# synchronous.net
KiCad netlist of a schematic drawn in Altium Designer
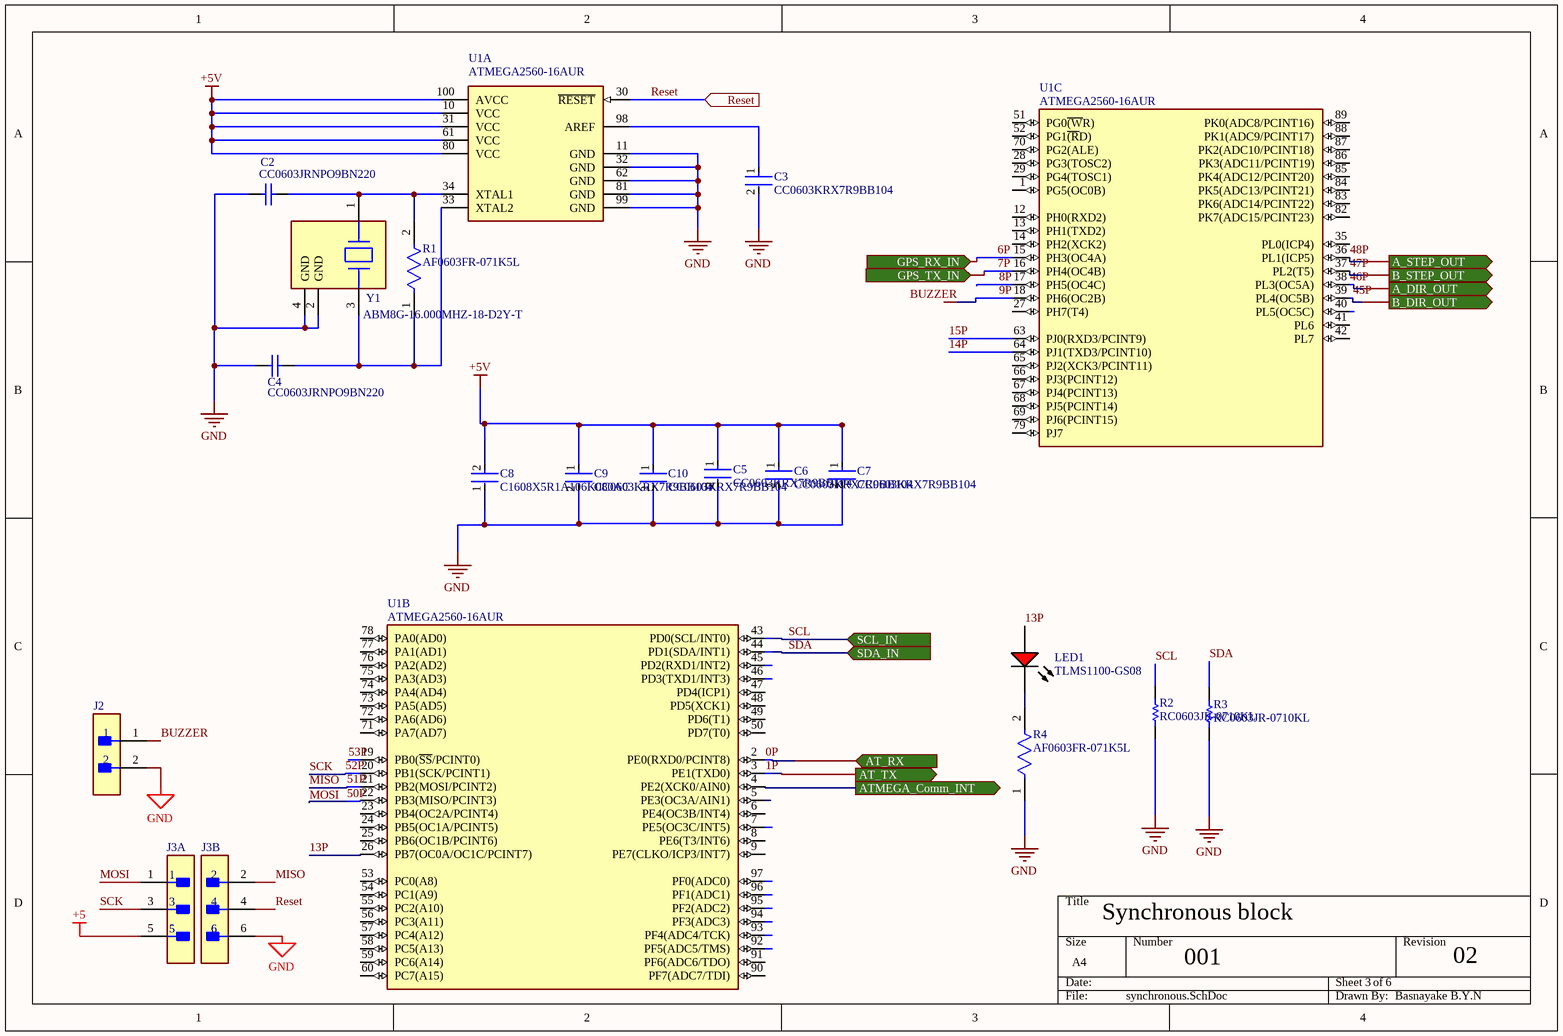
[diagram p0: synchronous.SchDoc]

(export (version "E")
  (design (tool "Eeschema 10.0.6"))
  (components
    (comp (ref "C2")
      (value "CC0603JRNPO9BN220")
      (footprint "CAPC1608X90X40LL10T20")
      (description "Chip Capacitor, 22 pF, +/- 5%, 50 V, -55 to 125 degC, 0603 (1608 Metric), RoHS, Tape and Reel")
      (libsource (lib "Altium Content Vault") (part "CAP-NP-2"))
    )
    (comp (ref "C3")
      (value "CC0603KRX7R9BB104")
      (footprint "FP-CC0603-DA-MFG")
      (description "CAP CER 0.1UF 50V X7R 0603")
      (fields (field (name "MANUFACTURER") "YAGEO") (field (name "VOLTAGE") "50 V"))
      (libsource (lib "Altium Content Vault") (part "11868f565c42a9108669ba33697ecf6"))
    )
    (comp (ref "C4")
      (value "CC0603JRNPO9BN220")
      (footprint "CAPC1608X90X40LL10T20")
      (description "Chip Capacitor, 22 pF, +/- 5%, 50 V, -55 to 125 degC, 0603 (1608 Metric), RoHS, Tape and Reel")
      (libsource (lib "Altium Content Vault") (part "CAP-NP-2"))
    )
    (comp (ref "C5")
      (value "CC0603KRX7R9BB104")
      (footprint "FP-CC0603-DA-MFG")
      (description "CAP CER 0.1UF 50V X7R 0603")
      (fields (field (name "MANUFACTURER") "YAGEO") (field (name "VOLTAGE") "50 V"))
      (libsource (lib "Altium Content Vault") (part "11868f565c42a9108669ba33697ecf6"))
    )
    (comp (ref "C6")
      (value "CC0603KRX7R9BB104")
      (footprint "FP-CC0603-DA-MFG")
      (description "CAP CER 0.1UF 50V X7R 0603")
      (fields (field (name "MANUFACTURER") "YAGEO") (field (name "VOLTAGE") "50 V"))
      (libsource (lib "Altium Content Vault") (part "11868f565c42a9108669ba33697ecf6"))
    )
    (comp (ref "C7")
      (value "CC0603KRX7R9BB104")
      (footprint "FP-CC0603-DA-MFG")
      (description "CAP CER 0.1UF 50V X7R 0603")
      (fields (field (name "MANUFACTURER") "YAGEO") (field (name "VOLTAGE") "50 V"))
      (libsource (lib "Altium Content Vault") (part "11868f565c42a9108669ba33697ecf6"))
    )
    (comp (ref "C8")
      (value "C1608X5R1A106K080AC")
      (footprint "FP-C1608-080-0_1-MFG")
      (description "Multilayer Ceramic Capacitors 10μF ±10% 10V X5R SMD 0603")
      (fields (field (name "VOLTAGE") "10V") (field (name "TOLERANCE") "10%"))
      (libsource (lib "Altium Content Vault") (part "236180d848d6139a670b325ea6854c9"))
    )
    (comp (ref "C9")
      (value "CC0603KRX7R9BB104")
      (footprint "FP-CC0603-DA-MFG")
      (description "CAP CER 0.1UF 50V X7R 0603")
      (fields (field (name "MANUFACTURER") "YAGEO") (field (name "VOLTAGE") "50 V"))
      (libsource (lib "Altium Content Vault") (part "11868f565c42a9108669ba33697ecf6"))
    )
    (comp (ref "C10")
      (value "CC0603KRX7R9BB104")
      (footprint "FP-CC0603-DA-MFG")
      (description "CAP CER 0.1UF 50V X7R 0603")
      (fields (field (name "MANUFACTURER") "YAGEO") (field (name "VOLTAGE") "50 V"))
      (libsource (lib "Altium Content Vault") (part "11868f565c42a9108669ba33697ecf6"))
    )
    (comp (ref "J2")
      (value "B2B-XH-A(LF)(SN)")
      (footprint "FP-B2B-XH-A_LF_SN-MFG")
      (description "CONN HEADER VERT 2POS 2.5MM")
      (libsource (lib "Altium Content Vault") (part "3bc925449376181038e59eaffc5286c"))
    )
    (comp (ref "J3")
      (value "M20-9980346")
      (footprint "FP-M20-9980346-MFG")
      (description "CONN HEADER VERT 6POS 2.54MM")
      (fields
        (field (name "MANUFACTURER") "Harwin")
        (field (name "OCTOPART") "https://octopart.com/m20-9980346-harwin-5436545")
      )
      (libsource (lib "") (part "2654a11fb13586ecb194516b1c997bc_1"))
    )
    (comp (ref "LED1")
      (value "TLMS1100-GS08")
      (footprint "VISH-TLMX1100_V")
      (description "LED, RED, 2.1 V, -40 to 100 degC, 2-Pin SMD (0603), RoHS, Tape and Reel")
      (fields (field (name "TOLERANCE") "5%"))
      (libsource (lib "Altium Content Vault") (part "LED-RED-AK-2"))
    )
    (comp (ref "R1")
      (value "AF0603FR-071K5L")
      (footprint "FP-AF0603-IPC_B")
      (description "Anti-Sulfurated Chip Resistors Automotive Grade 1.5kΩ 1% 100ppm/°C 0603")
      (fields (field (name "TOLERANCE") "1%"))
      (libsource (lib "Altium Content Vault") (part "1029c3af85768c4190bb7ad29bc67b5"))
    )
    (comp (ref "R2")
      (value "RC0603JR-0710KL")
      (footprint "RESC1608X55X25ML10T15")
      (description "Resistor, 10 KOhm, +/- 5%, 100 mW, -55 to 155 degC, 0603 (1608 Metric), RoHS, Tape and Reel")
      (fields (field (name "MANUFACTURER") "Yageo") (field (name "TOLERANCE") "5%"))
      (libsource (lib "Altium Content Vault") (part "RES-2"))
    )
    (comp (ref "R3")
      (value "RC0603JR-0710KL")
      (footprint "RESC1608X55X25ML10T15")
      (description "Resistor, 10 KOhm, +/- 5%, 100 mW, -55 to 155 degC, 0603 (1608 Metric), RoHS, Tape and Reel")
      (fields (field (name "MANUFACTURER") "Yageo") (field (name "TOLERANCE") "5%"))
      (libsource (lib "Altium Content Vault") (part "RES-2"))
    )
    (comp (ref "R4")
      (value "AF0603FR-071K5L")
      (footprint "FP-AF0603-IPC_B")
      (description "Anti-Sulfurated Chip Resistors Automotive Grade 1.5kΩ 1% 100ppm/°C 0603")
      (fields (field (name "TOLERANCE") "1%"))
      (libsource (lib "Altium Content Vault") (part "1029c3af85768c4190bb7ad29bc67b5"))
    )
    (comp (ref "U1")
      (value "ATMEGA2560-16AUR")
      (footprint "FP-100A-MFG")
      (description "IC MCU 8BIT 256KB FLASH 100TQFP")
      (libsource (lib "Altium Content Vault") (part "7a986b9e50de34ed0d2049ae6a26084"))
    )
    (comp (ref "Y1")
      (value "ABM8G-16.000MHZ-18-D2Y-T")
      (footprint "FP-ABM8G-MFG")
      (description "Crystal 12MHz ±20ppm (Tol) ±30ppm (Stability) 18pF FUND 120Ω 4-Pin SMD T/R")
      (fields (field (name "TOLERANCE") "20ppm"))
      (libsource (lib "Altium Content Vault") (part "48e526d86b7f2615d98721063c72f49"))
    )
  )
  (nets
    (net (code "1") (name "+5") (class "Default")
      (node (ref "J3") (pin "5") (pinfunction "5_5") (pintype "passive"))
    )
    (net (code "2") (name "+5V") (class "Default")
      (node (ref "C10") (pin "1") (pinfunction "1_1") (pintype "passive"))
      (node (ref "C5") (pin "1") (pinfunction "1_1") (pintype "passive"))
      (node (ref "C6") (pin "1") (pinfunction "1_1") (pintype "passive"))
      (node (ref "C7") (pin "1") (pinfunction "1_1") (pintype "passive"))
      (node (ref "C8") (pin "2") (pinfunction "2_2") (pintype "passive"))
      (node (ref "C9") (pin "1") (pinfunction "1_1") (pintype "passive"))
      (node (ref "U1") (pin "10") (pinfunction "VCC_10") (pintype "power_in"))
      (node (ref "U1") (pin "100") (pinfunction "AVCC_100") (pintype "power_in"))
      (node (ref "U1") (pin "31") (pinfunction "VCC_31") (pintype "power_in"))
      (node (ref "U1") (pin "61") (pinfunction "VCC_61") (pintype "power_in"))
      (node (ref "U1") (pin "80") (pinfunction "VCC_80") (pintype "power_in"))
    )
    (net (code "3") (name "/0P") (class "Default")
      (node (ref "U1") (pin "2") (pinfunction "PE0(RXD0/PCINT8)_2") (pintype "bidirectional"))
    )
    (net (code "4") (name "/1P") (class "Default")
      (node (ref "U1") (pin "3") (pinfunction "PE1(TXD0)_3") (pintype "bidirectional"))
    )
    (net (code "5") (name "/6P") (class "Default")
      (node (ref "U1") (pin "15") (pinfunction "PH3(OC4A)_15") (pintype "bidirectional"))
    )
    (net (code "6") (name "/7P") (class "Default")
      (node (ref "U1") (pin "16") (pinfunction "PH4(OC4B)_16") (pintype "bidirectional"))
    )
    (net (code "7") (name "/8P") (class "Default")
      (node (ref "U1") (pin "17") (pinfunction "PH5(OC4C)_17") (pintype "bidirectional"))
    )
    (net (code "8") (name "/9P") (class "Default")
      (node (ref "U1") (pin "18") (pinfunction "PH6(OC2B)_18") (pintype "bidirectional"))
    )
    (net (code "9") (name "/13P") (class "Default")
      (node (ref "LED1") (pin "1") (pinfunction "A_1") (pintype "passive"))
      (node (ref "U1") (pin "26") (pinfunction "PB7(OC0A/OC1C/PCINT7)_26") (pintype "bidirectional"))
    )
    (net (code "10") (name "/14P") (class "Default")
      (node (ref "U1") (pin "64") (pinfunction "PJ1(TXD3/PCINT10)_64") (pintype "bidirectional"))
    )
    (net (code "11") (name "/15P") (class "Default")
      (node (ref "U1") (pin "63") (pinfunction "PJ0(RXD3/PCINT9)_63") (pintype "bidirectional"))
    )
    (net (code "12") (name "/45P") (class "Default")
      (node (ref "U1") (pin "39") (pinfunction "PL4(OC5B)_39") (pintype "bidirectional"))
    )
    (net (code "13") (name "/46P") (class "Default")
      (node (ref "U1") (pin "38") (pinfunction "PL3(OC5A)_38") (pintype "bidirectional"))
    )
    (net (code "14") (name "/47P") (class "Default")
      (node (ref "U1") (pin "37") (pinfunction "PL2(T5)_37") (pintype "bidirectional"))
    )
    (net (code "15") (name "/48P") (class "Default")
      (node (ref "U1") (pin "36") (pinfunction "PL1(ICP5)_36") (pintype "bidirectional"))
    )
    (net (code "16") (name "/50P") (class "Default")
      (node (ref "J3") (pin "1") (pinfunction "1_1") (pintype "passive"))
      (node (ref "U1") (pin "22") (pinfunction "PB3(MISO/PCINT3)_22") (pintype "bidirectional"))
    )
    (net (code "18") (name "/52P") (class "Default")
      (node (ref "J3") (pin "3") (pinfunction "3_3") (pintype "passive"))
      (node (ref "U1") (pin "20") (pinfunction "PB1(SCK/PCINT1)_20") (pintype "bidirectional"))
    )
    (net (code "19") (name "/53P") (class "Default")
      (node (ref "U1") (pin "19") (pinfunction "PB0(~{SS}/PCINT0)_19") (pintype "bidirectional"))
    )
    (net (code "20") (name "/ATMEGA_Comm_INT") (class "Default")
      (node (ref "U1") (pin "4") (pinfunction "PE2(XCK0/AIN0)_4") (pintype "bidirectional"))
    )
    (net (code "21") (name "/BUZZER") (class "Default")
      (node (ref "J2") (pin "1") (pinfunction "1_1") (pintype "passive"))
    )
    (net (code "22") (name "/MISO") (class "Default")
      (node (ref "J3") (pin "2") (pinfunction "2_2") (pintype "passive"))
      (node (ref "U1") (pin "21") (pinfunction "PB2(MOSI/PCINT2)_21") (pintype "bidirectional"))
    )
    (net (code "23") (name "/Reset") (class "Default")
      (node (ref "J3") (pin "4") (pinfunction "4_4") (pintype "passive"))
      (node (ref "U1") (pin "30") (pinfunction "~{RESET}_30") (pintype "input"))
    )
    (net (code "24") (name "/SCL") (class "Default")
      (node (ref "R2") (pin "2") (pinfunction "2_2") (pintype "passive"))
      (node (ref "U1") (pin "43") (pinfunction "PD0(SCL/INT0)_43") (pintype "bidirectional"))
    )
    (net (code "25") (name "/SDA") (class "Default")
      (node (ref "R3") (pin "2") (pinfunction "2_2") (pintype "passive"))
      (node (ref "U1") (pin "44") (pinfunction "PD1(SDA/INT1)_44") (pintype "bidirectional"))
    )
    (net (code "26") (name "GND") (class "Default")
      (node (ref "C10") (pin "2") (pinfunction "2_2") (pintype "passive"))
      (node (ref "C2") (pin "1") (pinfunction "1_1") (pintype "passive"))
      (node (ref "C3") (pin "2") (pinfunction "2_2") (pintype "passive"))
      (node (ref "C4") (pin "1") (pinfunction "1_1") (pintype "passive"))
      (node (ref "C5") (pin "2") (pinfunction "2_2") (pintype "passive"))
      (node (ref "C6") (pin "2") (pinfunction "2_2") (pintype "passive"))
      (node (ref "C7") (pin "2") (pinfunction "2_2") (pintype "passive"))
      (node (ref "C8") (pin "1") (pinfunction "1_1") (pintype "passive"))
      (node (ref "C9") (pin "2") (pinfunction "2_2") (pintype "passive"))
      (node (ref "J2") (pin "2") (pinfunction "2_2") (pintype "passive"))
      (node (ref "J3") (pin "6") (pinfunction "6_6") (pintype "passive"))
      (node (ref "R2") (pin "1") (pinfunction "1_1") (pintype "passive"))
      (node (ref "R3") (pin "1") (pinfunction "1_1") (pintype "passive"))
      (node (ref "R4") (pin "1") (pinfunction "1_1") (pintype "passive"))
      (node (ref "U1") (pin "11") (pinfunction "GND_11") (pintype "power_in"))
      (node (ref "U1") (pin "32") (pinfunction "GND_32") (pintype "power_in"))
      (node (ref "U1") (pin "62") (pinfunction "GND_62") (pintype "power_in"))
      (node (ref "U1") (pin "81") (pinfunction "GND_81") (pintype "power_in"))
      (node (ref "U1") (pin "99") (pinfunction "GND_99") (pintype "power_in"))
      (node (ref "Y1") (pin "2") (pinfunction "GND_2") (pintype "power_in"))
      (node (ref "Y1") (pin "4") (pinfunction "GND_4") (pintype "power_in"))
    )
    (net (code "27") (name "Net-(LED1-K)") (class "Default")
      (node (ref "LED1") (pin "2") (pinfunction "K_2") (pintype "passive"))
      (node (ref "R4") (pin "2") (pinfunction "2_2") (pintype "passive"))
    )
    (net (code "28") (name "Net-(U1A-AREF)") (class "Default")
      (node (ref "C3") (pin "1") (pinfunction "1_1") (pintype "passive"))
      (node (ref "U1") (pin "98") (pinfunction "AREF_98") (pintype "passive"))
    )
    (net (code "29") (name "Net-(U1A-XTAL1)") (class "Default")
      (node (ref "C2") (pin "2") (pinfunction "2_2") (pintype "passive"))
      (node (ref "R1") (pin "2") (pinfunction "2_2") (pintype "passive"))
      (node (ref "U1") (pin "34") (pinfunction "XTAL1_34") (pintype "passive"))
      (node (ref "Y1") (pin "1") (pinfunction "1_1") (pintype "passive"))
    )
    (net (code "30") (name "Net-(U1A-XTAL2)") (class "Default")
      (node (ref "C4") (pin "2") (pinfunction "2_2") (pintype "passive"))
      (node (ref "R1") (pin "1") (pinfunction "1_1") (pintype "passive"))
      (node (ref "U1") (pin "33") (pinfunction "XTAL2_33") (pintype "passive"))
      (node (ref "Y1") (pin "3") (pinfunction "3_3") (pintype "passive"))
    )
    (net (code "31") (name "unconnected-(U1B-PA0(AD0)-Pad78)") (class "Default")
      (node (ref "U1") (pin "78") (pinfunction "PA0(AD0)_78") (pintype "bidirectional"))
    )
    (net (code "32") (name "unconnected-(U1B-PA1(AD1)-Pad77)") (class "Default")
      (node (ref "U1") (pin "77") (pinfunction "PA1(AD1)_77") (pintype "bidirectional"))
    )
    (net (code "33") (name "unconnected-(U1B-PA2(AD2)-Pad76)") (class "Default")
      (node (ref "U1") (pin "76") (pinfunction "PA2(AD2)_76") (pintype "bidirectional"))
    )
    (net (code "34") (name "unconnected-(U1B-PA3(AD3)-Pad75)") (class "Default")
      (node (ref "U1") (pin "75") (pinfunction "PA3(AD3)_75") (pintype "bidirectional"))
    )
    (net (code "35") (name "unconnected-(U1B-PA4(AD4)-Pad74)") (class "Default")
      (node (ref "U1") (pin "74") (pinfunction "PA4(AD4)_74") (pintype "bidirectional"))
    )
    (net (code "36") (name "unconnected-(U1B-PA5(AD5)-Pad73)") (class "Default")
      (node (ref "U1") (pin "73") (pinfunction "PA5(AD5)_73") (pintype "bidirectional"))
    )
    (net (code "37") (name "unconnected-(U1B-PA6(AD6)-Pad72)") (class "Default")
      (node (ref "U1") (pin "72") (pinfunction "PA6(AD6)_72") (pintype "bidirectional"))
    )
    (net (code "38") (name "unconnected-(U1B-PA7(AD7)-Pad71)") (class "Default")
      (node (ref "U1") (pin "71") (pinfunction "PA7(AD7)_71") (pintype "bidirectional"))
    )
    (net (code "39") (name "unconnected-(U1B-PB4(OC2A{slash}PCINT4)-Pad23)") (class "Default")
      (node (ref "U1") (pin "23") (pinfunction "PB4(OC2A/PCINT4)_23") (pintype "bidirectional"))
    )
    (net (code "40") (name "unconnected-(U1B-PB5(OC1A{slash}PCINT5)-Pad24)") (class "Default")
      (node (ref "U1") (pin "24") (pinfunction "PB5(OC1A/PCINT5)_24") (pintype "bidirectional"))
    )
    (net (code "41") (name "unconnected-(U1B-PB6(OC1B{slash}PCINT6)-Pad25)") (class "Default")
      (node (ref "U1") (pin "25") (pinfunction "PB6(OC1B/PCINT6)_25") (pintype "bidirectional"))
    )
    (net (code "42") (name "unconnected-(U1B-PC0(A8)-Pad53)") (class "Default")
      (node (ref "U1") (pin "53") (pinfunction "PC0(A8)_53") (pintype "bidirectional"))
    )
    (net (code "43") (name "unconnected-(U1B-PC1(A9)-Pad54)") (class "Default")
      (node (ref "U1") (pin "54") (pinfunction "PC1(A9)_54") (pintype "bidirectional"))
    )
    (net (code "44") (name "unconnected-(U1B-PC2(A10)-Pad55)") (class "Default")
      (node (ref "U1") (pin "55") (pinfunction "PC2(A10)_55") (pintype "bidirectional"))
    )
    (net (code "45") (name "unconnected-(U1B-PC3(A11)-Pad56)") (class "Default")
      (node (ref "U1") (pin "56") (pinfunction "PC3(A11)_56") (pintype "bidirectional"))
    )
    (net (code "46") (name "unconnected-(U1B-PC4(A12)-Pad57)") (class "Default")
      (node (ref "U1") (pin "57") (pinfunction "PC4(A12)_57") (pintype "bidirectional"))
    )
    (net (code "47") (name "unconnected-(U1B-PC5(A13)-Pad58)") (class "Default")
      (node (ref "U1") (pin "58") (pinfunction "PC5(A13)_58") (pintype "bidirectional"))
    )
    (net (code "48") (name "unconnected-(U1B-PC6(A14)-Pad59)") (class "Default")
      (node (ref "U1") (pin "59") (pinfunction "PC6(A14)_59") (pintype "bidirectional"))
    )
    (net (code "49") (name "unconnected-(U1B-PC7(A15)-Pad60)") (class "Default")
      (node (ref "U1") (pin "60") (pinfunction "PC7(A15)_60") (pintype "bidirectional"))
    )
    (net (code "50") (name "unconnected-(U1B-PD2(RXD1{slash}INT2)-Pad45)") (class "Default")
      (node (ref "U1") (pin "45") (pinfunction "PD2(RXD1/INT2)_45") (pintype "bidirectional"))
    )
    (net (code "51") (name "unconnected-(U1B-PD3(TXD1{slash}INT3)-Pad46)") (class "Default")
      (node (ref "U1") (pin "46") (pinfunction "PD3(TXD1/INT3)_46") (pintype "bidirectional"))
    )
    (net (code "52") (name "unconnected-(U1B-PD4(ICP1)-Pad47)") (class "Default")
      (node (ref "U1") (pin "47") (pinfunction "PD4(ICP1)_47") (pintype "bidirectional"))
    )
    (net (code "53") (name "unconnected-(U1B-PD5(XCK1)-Pad48)") (class "Default")
      (node (ref "U1") (pin "48") (pinfunction "PD5(XCK1)_48") (pintype "bidirectional"))
    )
    (net (code "54") (name "unconnected-(U1B-PD6(T1)-Pad49)") (class "Default")
      (node (ref "U1") (pin "49") (pinfunction "PD6(T1)_49") (pintype "bidirectional"))
    )
    (net (code "55") (name "unconnected-(U1B-PD7(T0)-Pad50)") (class "Default")
      (node (ref "U1") (pin "50") (pinfunction "PD7(T0)_50") (pintype "bidirectional"))
    )
    (net (code "56") (name "unconnected-(U1B-PE3(OC3A{slash}AIN1)-Pad5)") (class "Default")
      (node (ref "U1") (pin "5") (pinfunction "PE3(OC3A/AIN1)_5") (pintype "bidirectional"))
    )
    (net (code "57") (name "unconnected-(U1B-PE4(OC3B{slash}INT4)-Pad6)") (class "Default")
      (node (ref "U1") (pin "6") (pinfunction "PE4(OC3B/INT4)_6") (pintype "bidirectional"))
    )
    (net (code "58") (name "unconnected-(U1B-PE5(OC3C{slash}INT5)-Pad7)") (class "Default")
      (node (ref "U1") (pin "7") (pinfunction "PE5(OC3C/INT5)_7") (pintype "bidirectional"))
    )
    (net (code "59") (name "unconnected-(U1B-PE6(T3{slash}INT6)-Pad8)") (class "Default")
      (node (ref "U1") (pin "8") (pinfunction "PE6(T3/INT6)_8") (pintype "bidirectional"))
    )
    (net (code "60") (name "unconnected-(U1B-PE7(CLKO{slash}ICP3{slash}INT7)-Pad9)") (class "Default")
      (node (ref "U1") (pin "9") (pinfunction "PE7(CLKO/ICP3/INT7)_9") (pintype "bidirectional"))
    )
    (net (code "61") (name "unconnected-(U1B-PF0(ADC0)-Pad97)") (class "Default")
      (node (ref "U1") (pin "97") (pinfunction "PF0(ADC0)_97") (pintype "bidirectional"))
    )
    (net (code "62") (name "unconnected-(U1B-PF1(ADC1)-Pad96)") (class "Default")
      (node (ref "U1") (pin "96") (pinfunction "PF1(ADC1)_96") (pintype "bidirectional"))
    )
    (net (code "63") (name "unconnected-(U1B-PF2(ADC2)-Pad95)") (class "Default")
      (node (ref "U1") (pin "95") (pinfunction "PF2(ADC2)_95") (pintype "bidirectional"))
    )
    (net (code "64") (name "unconnected-(U1B-PF3(ADC3)-Pad94)") (class "Default")
      (node (ref "U1") (pin "94") (pinfunction "PF3(ADC3)_94") (pintype "bidirectional"))
    )
    (net (code "65") (name "unconnected-(U1B-PF4(ADC4{slash}TCK)-Pad93)") (class "Default")
      (node (ref "U1") (pin "93") (pinfunction "PF4(ADC4/TCK)_93") (pintype "bidirectional"))
    )
    (net (code "66") (name "unconnected-(U1B-PF5(ADC5{slash}TMS)-Pad92)") (class "Default")
      (node (ref "U1") (pin "92") (pinfunction "PF5(ADC5/TMS)_92") (pintype "bidirectional"))
    )
    (net (code "67") (name "unconnected-(U1B-PF6(ADC6{slash}TDO)-Pad91)") (class "Default")
      (node (ref "U1") (pin "91") (pinfunction "PF6(ADC6/TDO)_91") (pintype "bidirectional"))
    )
    (net (code "68") (name "unconnected-(U1B-PF7(ADC7{slash}TDI)-Pad90)") (class "Default")
      (node (ref "U1") (pin "90") (pinfunction "PF7(ADC7/TDI)_90") (pintype "bidirectional"))
    )
    (net (code "69") (name "unconnected-(U1C-PG0~{(W}R)-Pad51)") (class "Default")
      (node (ref "U1") (pin "51") (pinfunction "PG0~{(W}R)_51") (pintype "bidirectional"))
    )
    (net (code "70") (name "unconnected-(U1C-PG1~{(R}D)-Pad52)") (class "Default")
      (node (ref "U1") (pin "52") (pinfunction "PG1~{(R}D)_52") (pintype "bidirectional"))
    )
    (net (code "71") (name "unconnected-(U1C-PG2(ALE)-Pad70)") (class "Default")
      (node (ref "U1") (pin "70") (pinfunction "PG2(ALE)_70") (pintype "bidirectional"))
    )
    (net (code "72") (name "unconnected-(U1C-PG3(TOSC2)-Pad28)") (class "Default")
      (node (ref "U1") (pin "28") (pinfunction "PG3(TOSC2)_28") (pintype "bidirectional"))
    )
    (net (code "73") (name "unconnected-(U1C-PG4(TOSC1)-Pad29)") (class "Default")
      (node (ref "U1") (pin "29") (pinfunction "PG4(TOSC1)_29") (pintype "bidirectional"))
    )
    (net (code "74") (name "unconnected-(U1C-PG5(OC0B)-Pad1)") (class "Default")
      (node (ref "U1") (pin "1") (pinfunction "PG5(OC0B)_1") (pintype "bidirectional"))
    )
    (net (code "75") (name "unconnected-(U1C-PH0(RXD2)-Pad12)") (class "Default")
      (node (ref "U1") (pin "12") (pinfunction "PH0(RXD2)_12") (pintype "bidirectional"))
    )
    (net (code "76") (name "unconnected-(U1C-PH1(TXD2)-Pad13)") (class "Default")
      (node (ref "U1") (pin "13") (pinfunction "PH1(TXD2)_13") (pintype "bidirectional"))
    )
    (net (code "77") (name "unconnected-(U1C-PH2(XCK2)-Pad14)") (class "Default")
      (node (ref "U1") (pin "14") (pinfunction "PH2(XCK2)_14") (pintype "bidirectional"))
    )
    (net (code "78") (name "unconnected-(U1C-PH7(T4)-Pad27)") (class "Default")
      (node (ref "U1") (pin "27") (pinfunction "PH7(T4)_27") (pintype "bidirectional"))
    )
    (net (code "79") (name "unconnected-(U1C-PJ2(XCK3{slash}PCINT11)-Pad65)") (class "Default")
      (node (ref "U1") (pin "65") (pinfunction "PJ2(XCK3/PCINT11)_65") (pintype "bidirectional"))
    )
    (net (code "80") (name "unconnected-(U1C-PJ3(PCINT12)-Pad66)") (class "Default")
      (node (ref "U1") (pin "66") (pinfunction "PJ3(PCINT12)_66") (pintype "bidirectional"))
    )
    (net (code "81") (name "unconnected-(U1C-PJ4(PCINT13)-Pad67)") (class "Default")
      (node (ref "U1") (pin "67") (pinfunction "PJ4(PCINT13)_67") (pintype "bidirectional"))
    )
    (net (code "82") (name "unconnected-(U1C-PJ5(PCINT14)-Pad68)") (class "Default")
      (node (ref "U1") (pin "68") (pinfunction "PJ5(PCINT14)_68") (pintype "bidirectional"))
    )
    (net (code "83") (name "unconnected-(U1C-PJ6(PCINT15)-Pad69)") (class "Default")
      (node (ref "U1") (pin "69") (pinfunction "PJ6(PCINT15)_69") (pintype "bidirectional"))
    )
    (net (code "84") (name "unconnected-(U1C-PJ7-Pad79)") (class "Default")
      (node (ref "U1") (pin "79") (pinfunction "PJ7_79") (pintype "bidirectional"))
    )
    (net (code "85") (name "unconnected-(U1C-PK0(ADC8{slash}PCINT16)-Pad89)") (class "Default")
      (node (ref "U1") (pin "89") (pinfunction "PK0(ADC8/PCINT16)_89") (pintype "bidirectional"))
    )
    (net (code "86") (name "unconnected-(U1C-PK1(ADC9{slash}PCINT17)-Pad88)") (class "Default")
      (node (ref "U1") (pin "88") (pinfunction "PK1(ADC9/PCINT17)_88") (pintype "bidirectional"))
    )
    (net (code "87") (name "unconnected-(U1C-PK2(ADC10{slash}PCINT18)-Pad87)") (class "Default")
      (node (ref "U1") (pin "87") (pinfunction "PK2(ADC10/PCINT18)_87") (pintype "bidirectional"))
    )
    (net (code "88") (name "unconnected-(U1C-PK3(ADC11{slash}PCINT19)-Pad86)") (class "Default")
      (node (ref "U1") (pin "86") (pinfunction "PK3(ADC11/PCINT19)_86") (pintype "bidirectional"))
    )
    (net (code "89") (name "unconnected-(U1C-PK4(ADC12{slash}PCINT20)-Pad85)") (class "Default")
      (node (ref "U1") (pin "85") (pinfunction "PK4(ADC12/PCINT20)_85") (pintype "bidirectional"))
    )
    (net (code "90") (name "unconnected-(U1C-PK5(ADC13{slash}PCINT21)-Pad84)") (class "Default")
      (node (ref "U1") (pin "84") (pinfunction "PK5(ADC13/PCINT21)_84") (pintype "bidirectional"))
    )
    (net (code "91") (name "unconnected-(U1C-PK6(ADC14{slash}PCINT22)-Pad83)") (class "Default")
      (node (ref "U1") (pin "83") (pinfunction "PK6(ADC14/PCINT22)_83") (pintype "bidirectional"))
    )
    (net (code "92") (name "unconnected-(U1C-PK7(ADC15{slash}PCINT23)-Pad82)") (class "Default")
      (node (ref "U1") (pin "82") (pinfunction "PK7(ADC15/PCINT23)_82") (pintype "bidirectional"))
    )
    (net (code "93") (name "unconnected-(U1C-PL0(ICP4)-Pad35)") (class "Default")
      (node (ref "U1") (pin "35") (pinfunction "PL0(ICP4)_35") (pintype "bidirectional"))
    )
    (net (code "94") (name "unconnected-(U1C-PL5(OC5C)-Pad40)") (class "Default")
      (node (ref "U1") (pin "40") (pinfunction "PL5(OC5C)_40") (pintype "bidirectional"))
    )
    (net (code "95") (name "unconnected-(U1C-PL6-Pad41)") (class "Default")
      (node (ref "U1") (pin "41") (pinfunction "PL6_41") (pintype "bidirectional"))
    )
    (net (code "96") (name "unconnected-(U1C-PL7-Pad42)") (class "Default")
      (node (ref "U1") (pin "42") (pinfunction "PL7_42") (pintype "bidirectional"))
    )
  )
)
